# 2_Power.net
KiCad netlist of a schematic drawn in Altium Designer
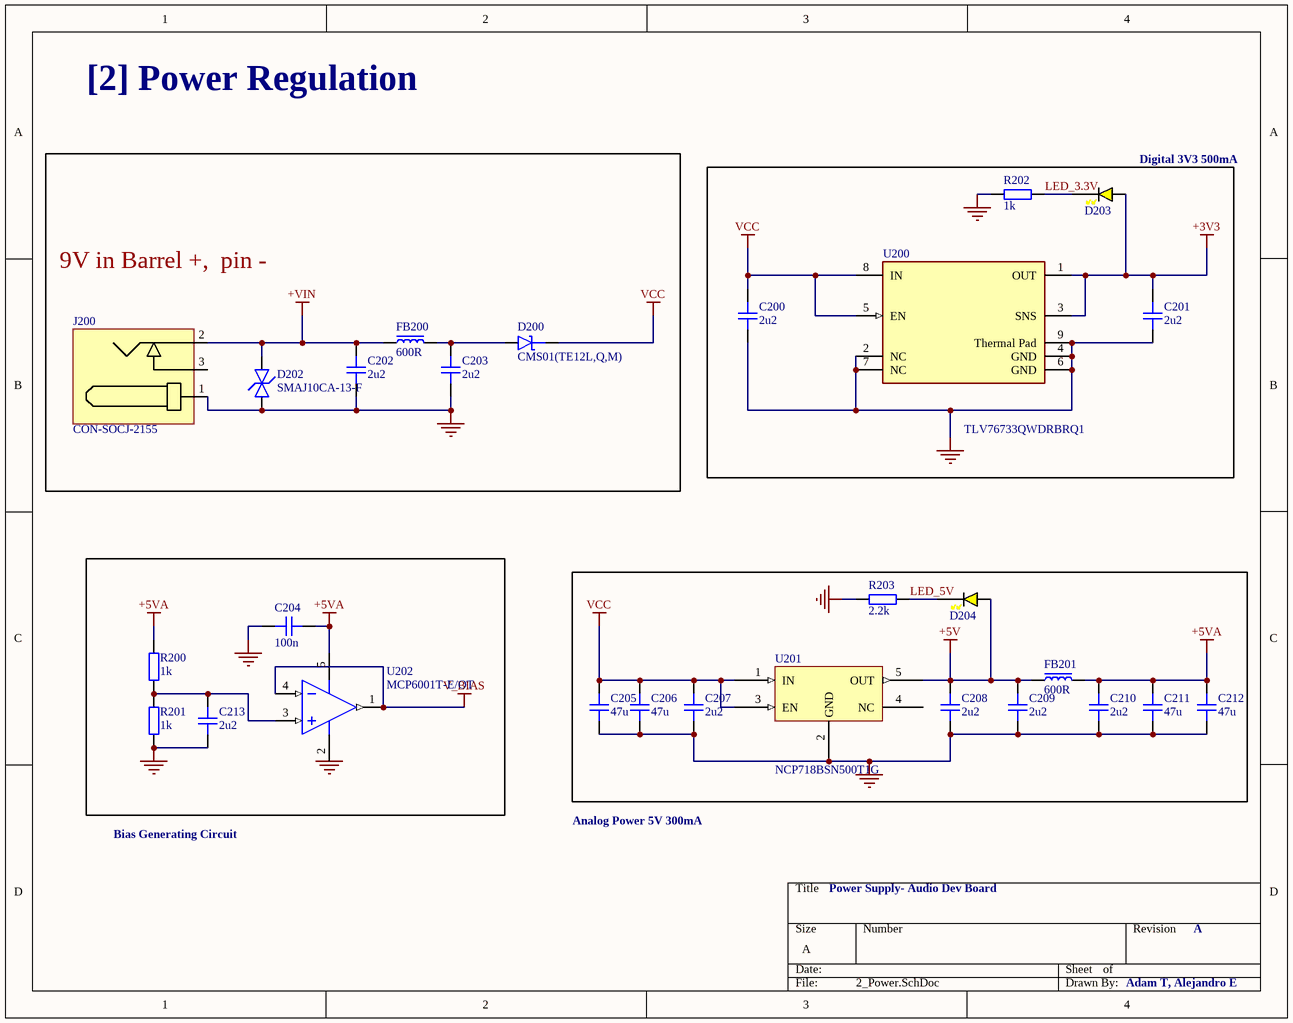
[diagram p0: 2_Power.SchDoc]

(export (version "E")
  (design (tool "Eeschema 10.0.6"))
  (components
    (comp (ref "C200")
      (value "2u2")
      (footprint "CAP_0402")
      (description "Capacitor SMD 0402")
      (libsource (lib "Schematic-Lib-PhilsLab") (part "CAP_0402"))
    )
    (comp (ref "C201")
      (value "2u2")
      (footprint "CAP_0402")
      (description "Capacitor SMD 0402")
      (libsource (lib "Schematic-Lib-PhilsLab") (part "CAP_0402"))
    )
    (comp (ref "C202")
      (value "2u2")
      (footprint "CAP_0402")
      (description "Capacitor SMD 0402")
      (libsource (lib "Schematic-Lib-PhilsLab") (part "CAP_0402"))
    )
    (comp (ref "C203")
      (value "2u2")
      (footprint "CAP_0402")
      (description "Capacitor SMD 0402")
      (libsource (lib "Schematic-Lib-PhilsLab") (part "CAP_0402"))
    )
    (comp (ref "C204")
      (value "100n")
      (footprint "CAP_0402")
      (description "Capacitor SMD 0402")
      (libsource (lib "Schematic-Lib-PhilsLab") (part "CAP_0402"))
    )
    (comp (ref "C205")
      (value "47u")
      (footprint "CAP_1210")
      (description "Capacitor SMD 1210")
      (libsource (lib "Schematic-Lib-PhilsLab") (part "CAP_1210"))
    )
    (comp (ref "C206")
      (value "47u")
      (footprint "CAP_1210")
      (description "Capacitor SMD 1210")
      (libsource (lib "Schematic-Lib-PhilsLab") (part "CAP_1210"))
    )
    (comp (ref "C207")
      (value "2u2")
      (footprint "CAP_0402")
      (description "Capacitor SMD 0402")
      (libsource (lib "Schematic-Lib-PhilsLab") (part "CAP_0402"))
    )
    (comp (ref "C208")
      (value "2u2")
      (footprint "CAP_0402")
      (description "Capacitor SMD 0402")
      (libsource (lib "Schematic-Lib-PhilsLab") (part "CAP_0402"))
    )
    (comp (ref "C209")
      (value "2u2")
      (footprint "CAP_0402")
      (description "Capacitor SMD 0402")
      (libsource (lib "Schematic-Lib-PhilsLab") (part "CAP_0402"))
    )
    (comp (ref "C210")
      (value "2u2")
      (footprint "CAP_0402")
      (description "Capacitor SMD 0402")
      (libsource (lib "Schematic-Lib-PhilsLab") (part "CAP_0402"))
    )
    (comp (ref "C211")
      (value "47u")
      (footprint "CAP_1210")
      (description "Capacitor SMD 1210")
      (libsource (lib "Schematic-Lib-PhilsLab") (part "CAP_1210"))
    )
    (comp (ref "C212")
      (value "47u")
      (footprint "CAP_1210")
      (description "Capacitor SMD 1210")
      (libsource (lib "Schematic-Lib-PhilsLab") (part "CAP_1210"))
    )
    (comp (ref "C213")
      (value "2u2")
      (footprint "CAP_0402")
      (description "Capacitor SMD 0402")
      (libsource (lib "Schematic-Lib-PhilsLab") (part "CAP_0402"))
    )
    (comp (ref "D200")
      (value "CMS01(TE12L,Q,M)")
      (footprint "SOD_128")
      (description "Diode 30 V 3A Surface Mount M-FLAT (2.4x3.8)\r\nSOD-128")
      (libsource (lib "Schematic-Lib-PhilsLab") (part "D_SCHOTTKY_SOD_128"))
    )
    (comp (ref "D202")
      (value "SMAJ10CA-13-F")
      (footprint "SMAJ10CA-13-F")
      (description "TVS DIODE 10VWM 17VC SMA (DO-214AC)")
      (libsource (lib "Schematic-Lib-PhilsLab") (part "SMAJ10CA-13-F"))
    )
    (comp (ref "D203")
      (value "YELLOW")
      (footprint "LED_0402_YELLOW")
      (description "LED 0402 YELLOW SMD")
      (libsource (lib "Schematic-Lib-PhilsLab") (part "LED_0402_YELLOW"))
    )
    (comp (ref "D204")
      (value "YELLOW")
      (footprint "LED_0402_YELLOW")
      (description "LED 0402 YELLOW SMD")
      (libsource (lib "Schematic-Lib-PhilsLab") (part "LED_0402_YELLOW"))
    )
    (comp (ref "FB200")
      (value "600R")
      (footprint "FB_0805")
      (description "Ferrite Bead SMD 0805 C2982098")
      (libsource (lib "Schematic-Lib-PhilsLab") (part "FB_0805"))
    )
    (comp (ref "FB201")
      (value "600R")
      (footprint "FB_0805")
      (description "Ferrite Bead SMD 0805 C2982098")
      (libsource (lib "Schematic-Lib-PhilsLab") (part "FB_0805"))
    )
    (comp (ref "J200")
      (value "CON-SOCJ-2155")
      (footprint "CON-SOCJ-2155")
      (description "DC Barrell Jack 2.1mm 30V 2.5A THT")
      (fields (field (name "MANUFACTURER") "Gravitech"))
      (libsource (lib "Schematic-Lib-PhilsLab") (part "CON-SOCJ-2155"))
    )
    (comp (ref "R200")
      (value "1k")
      (footprint "RES_0402")
      (description "Resistor SMD 0402")
      (libsource (lib "Schematic-Lib-PhilsLab") (part "RES_0402"))
    )
    (comp (ref "R201")
      (value "1k")
      (footprint "RES_0402")
      (description "Resistor SMD 0402")
      (libsource (lib "Schematic-Lib-PhilsLab") (part "RES_0402"))
    )
    (comp (ref "R202")
      (value "1k")
      (footprint "RES_0402")
      (description "Resistor SMD 0402")
      (libsource (lib "Schematic-Lib-PhilsLab") (part "RES_0402"))
    )
    (comp (ref "R203")
      (value "2.2k")
      (footprint "RES_0402")
      (description "Resistor SMD 0402")
      (libsource (lib "Schematic-Lib-PhilsLab") (part "RES_0402"))
    )
    (comp (ref "U200")
      (value "TLV76733QWDRBRQ1")
      (footprint "FP-DRB0008J-IPC_C")
      (description "IC OPAMP")
      (libsource (lib "Altium Content Vault") (part "986f8d1759350ee61d4b04c225c65ee"))
    )
    (comp (ref "U201")
      (value "NCP718BSN500T1G")
      (footprint "TSOT25")
      (description "Linear Voltage Regulator IC Positive Fixed 1 Output 300mA TSOT-23-5")
      (libsource (lib "Schematic-Lib-PhilsLab") (part "NCP718BSN500T1G"))
    )
    (comp (ref "U202")
      (value "MCP6001T-E/OT")
      (footprint "SOT-23-OT5_L")
      (description "None")
      (fields (field (name "VOLTAGE") "6V"))
      (libsource (lib "Altium Content Vault") (part "AMP-OPA-MCP6001-SOT5"))
    )
  )
  (nets
    (net (code "1") (name "+3V3") (class "Default")
      (node (ref "C201") (pin "2") (pinfunction "2_2") (pintype "passive"))
      (node (ref "D203") (pin "A") (pinfunction "A_A") (pintype "passive"))
      (node (ref "U200") (pin "1") (pinfunction "OUT_1") (pintype "power_in"))
      (node (ref "U200") (pin "3") (pinfunction "SNS_3") (pintype "passive"))
    )
    (net (code "2") (name "+5V") (class "Default")
      (node (ref "C208") (pin "2") (pinfunction "2_2") (pintype "passive"))
      (node (ref "C209") (pin "2") (pinfunction "2_2") (pintype "passive"))
      (node (ref "D204") (pin "A") (pinfunction "A_A") (pintype "passive"))
      (node (ref "FB201") (pin "1") (pinfunction "1_1") (pintype "passive"))
      (node (ref "U201") (pin "5") (pinfunction "OUT_5") (pintype "output"))
    )
    (net (code "3") (name "+5VA") (class "Default")
      (node (ref "C204") (pin "1") (pinfunction "1_1") (pintype "passive"))
      (node (ref "C210") (pin "2") (pinfunction "2_2") (pintype "passive"))
      (node (ref "C211") (pin "2") (pinfunction "2_2") (pintype "passive"))
      (node (ref "C212") (pin "2") (pinfunction "2_2") (pintype "passive"))
      (node (ref "FB201") (pin "2") (pinfunction "2_2") (pintype "passive"))
      (node (ref "R200") (pin "2") (pinfunction "2_2") (pintype "passive"))
      (node (ref "U202") (pin "5") (pinfunction "VDD_5") (pintype "power_in"))
    )
    (net (code "4") (name "+VIN") (class "Default")
      (node (ref "C202") (pin "2") (pinfunction "2_2") (pintype "passive"))
      (node (ref "D202") (pin "K") (pinfunction "K_K") (pintype "passive"))
      (node (ref "FB200") (pin "1") (pinfunction "1_1") (pintype "passive"))
      (node (ref "J200") (pin "2") (pinfunction "2_2") (pintype "passive"))
    )
    (net (code "5") (name "/LED_3.3V") (class "Default")
      (node (ref "D203") (pin "K") (pinfunction "K_K") (pintype "passive"))
      (node (ref "R202") (pin "2") (pinfunction "2_2") (pintype "passive"))
    )
    (net (code "6") (name "/LED_5V") (class "Default")
      (node (ref "D204") (pin "K") (pinfunction "K_K") (pintype "passive"))
      (node (ref "R203") (pin "2") (pinfunction "2_2") (pintype "passive"))
    )
    (net (code "7") (name "GND") (class "Default")
      (node (ref "C200") (pin "1") (pinfunction "1_1") (pintype "passive"))
      (node (ref "C201") (pin "1") (pinfunction "1_1") (pintype "passive"))
      (node (ref "C202") (pin "1") (pinfunction "1_1") (pintype "passive"))
      (node (ref "C203") (pin "1") (pinfunction "1_1") (pintype "passive"))
      (node (ref "C204") (pin "2") (pinfunction "2_2") (pintype "passive"))
      (node (ref "C205") (pin "1") (pinfunction "1_1") (pintype "passive"))
      (node (ref "C206") (pin "1") (pinfunction "1_1") (pintype "passive"))
      (node (ref "C207") (pin "1") (pinfunction "1_1") (pintype "passive"))
      (node (ref "C208") (pin "1") (pinfunction "1_1") (pintype "passive"))
      (node (ref "C209") (pin "1") (pinfunction "1_1") (pintype "passive"))
      (node (ref "C210") (pin "1") (pinfunction "1_1") (pintype "passive"))
      (node (ref "C211") (pin "1") (pinfunction "1_1") (pintype "passive"))
      (node (ref "C212") (pin "1") (pinfunction "1_1") (pintype "passive"))
      (node (ref "C213") (pin "1") (pinfunction "1_1") (pintype "passive"))
      (node (ref "D202") (pin "A") (pinfunction "A_A") (pintype "passive"))
      (node (ref "J200") (pin "1") (pinfunction "1_1") (pintype "passive"))
      (node (ref "R201") (pin "1") (pinfunction "1_1") (pintype "passive"))
      (node (ref "R202") (pin "1") (pinfunction "1_1") (pintype "passive"))
      (node (ref "R203") (pin "1") (pinfunction "1_1") (pintype "passive"))
      (node (ref "U200") (pin "2") (pinfunction "NC_2") (pintype "passive"))
      (node (ref "U200") (pin "4") (pinfunction "GND_4") (pintype "power_in"))
      (node (ref "U200") (pin "6") (pinfunction "GND_6") (pintype "power_in"))
      (node (ref "U200") (pin "7") (pinfunction "NC_7") (pintype "passive"))
      (node (ref "U200") (pin "9") (pinfunction "Thermal_Pad_9") (pintype "passive"))
      (node (ref "U201") (pin "2") (pinfunction "GND_2") (pintype "passive"))
      (node (ref "U202") (pin "2") (pinfunction "VSS_2") (pintype "power_in"))
    )
    (net (code "8") (name "Net-(C203-Pad2)") (class "Default")
      (node (ref "C203") (pin "2") (pinfunction "2_2") (pintype "passive"))
      (node (ref "D200") (pin "A") (pinfunction "A_A") (pintype "passive"))
      (node (ref "FB200") (pin "2") (pinfunction "2_2") (pintype "passive"))
    )
    (net (code "9") (name "Net-(U202-VIN+)") (class "Default")
      (node (ref "C213") (pin "2") (pinfunction "2_2") (pintype "passive"))
      (node (ref "R200") (pin "1") (pinfunction "1_1") (pintype "passive"))
      (node (ref "R201") (pin "2") (pinfunction "2_2") (pintype "passive"))
      (node (ref "U202") (pin "3") (pinfunction "VIN+_3") (pintype "input"))
    )
    (net (code "10") (name "VCC") (class "Default")
      (node (ref "C200") (pin "2") (pinfunction "2_2") (pintype "passive"))
      (node (ref "C205") (pin "2") (pinfunction "2_2") (pintype "passive"))
      (node (ref "C206") (pin "2") (pinfunction "2_2") (pintype "passive"))
      (node (ref "C207") (pin "2") (pinfunction "2_2") (pintype "passive"))
      (node (ref "D200") (pin "K") (pinfunction "K_K") (pintype "passive"))
      (node (ref "U200") (pin "5") (pinfunction "EN_5") (pintype "input"))
      (node (ref "U200") (pin "8") (pinfunction "IN_8") (pintype "power_in"))
      (node (ref "U201") (pin "1") (pinfunction "IN_1") (pintype "input"))
      (node (ref "U201") (pin "3") (pinfunction "EN_3") (pintype "input"))
    )
    (net (code "11") (name "V_BIAS") (class "Default")
      (node (ref "U202") (pin "1") (pinfunction "VOUT_1") (pintype "output"))
      (node (ref "U202") (pin "4") (pinfunction "VIN-_4") (pintype "input"))
    )
    (net (code "12") (name "unconnected-(J200-Pad3)") (class "Default")
      (node (ref "J200") (pin "3") (pinfunction "3_3") (pintype "passive"))
    )
    (net (code "13") (name "unconnected-(U201-NC-Pad4)") (class "Default")
      (node (ref "U201") (pin "4") (pinfunction "NC_4") (pintype "passive"))
    )
  )
)
